# 2_classyTKL_EC_matrix.net
KiCad netlist of a schematic drawn in Altium Designer
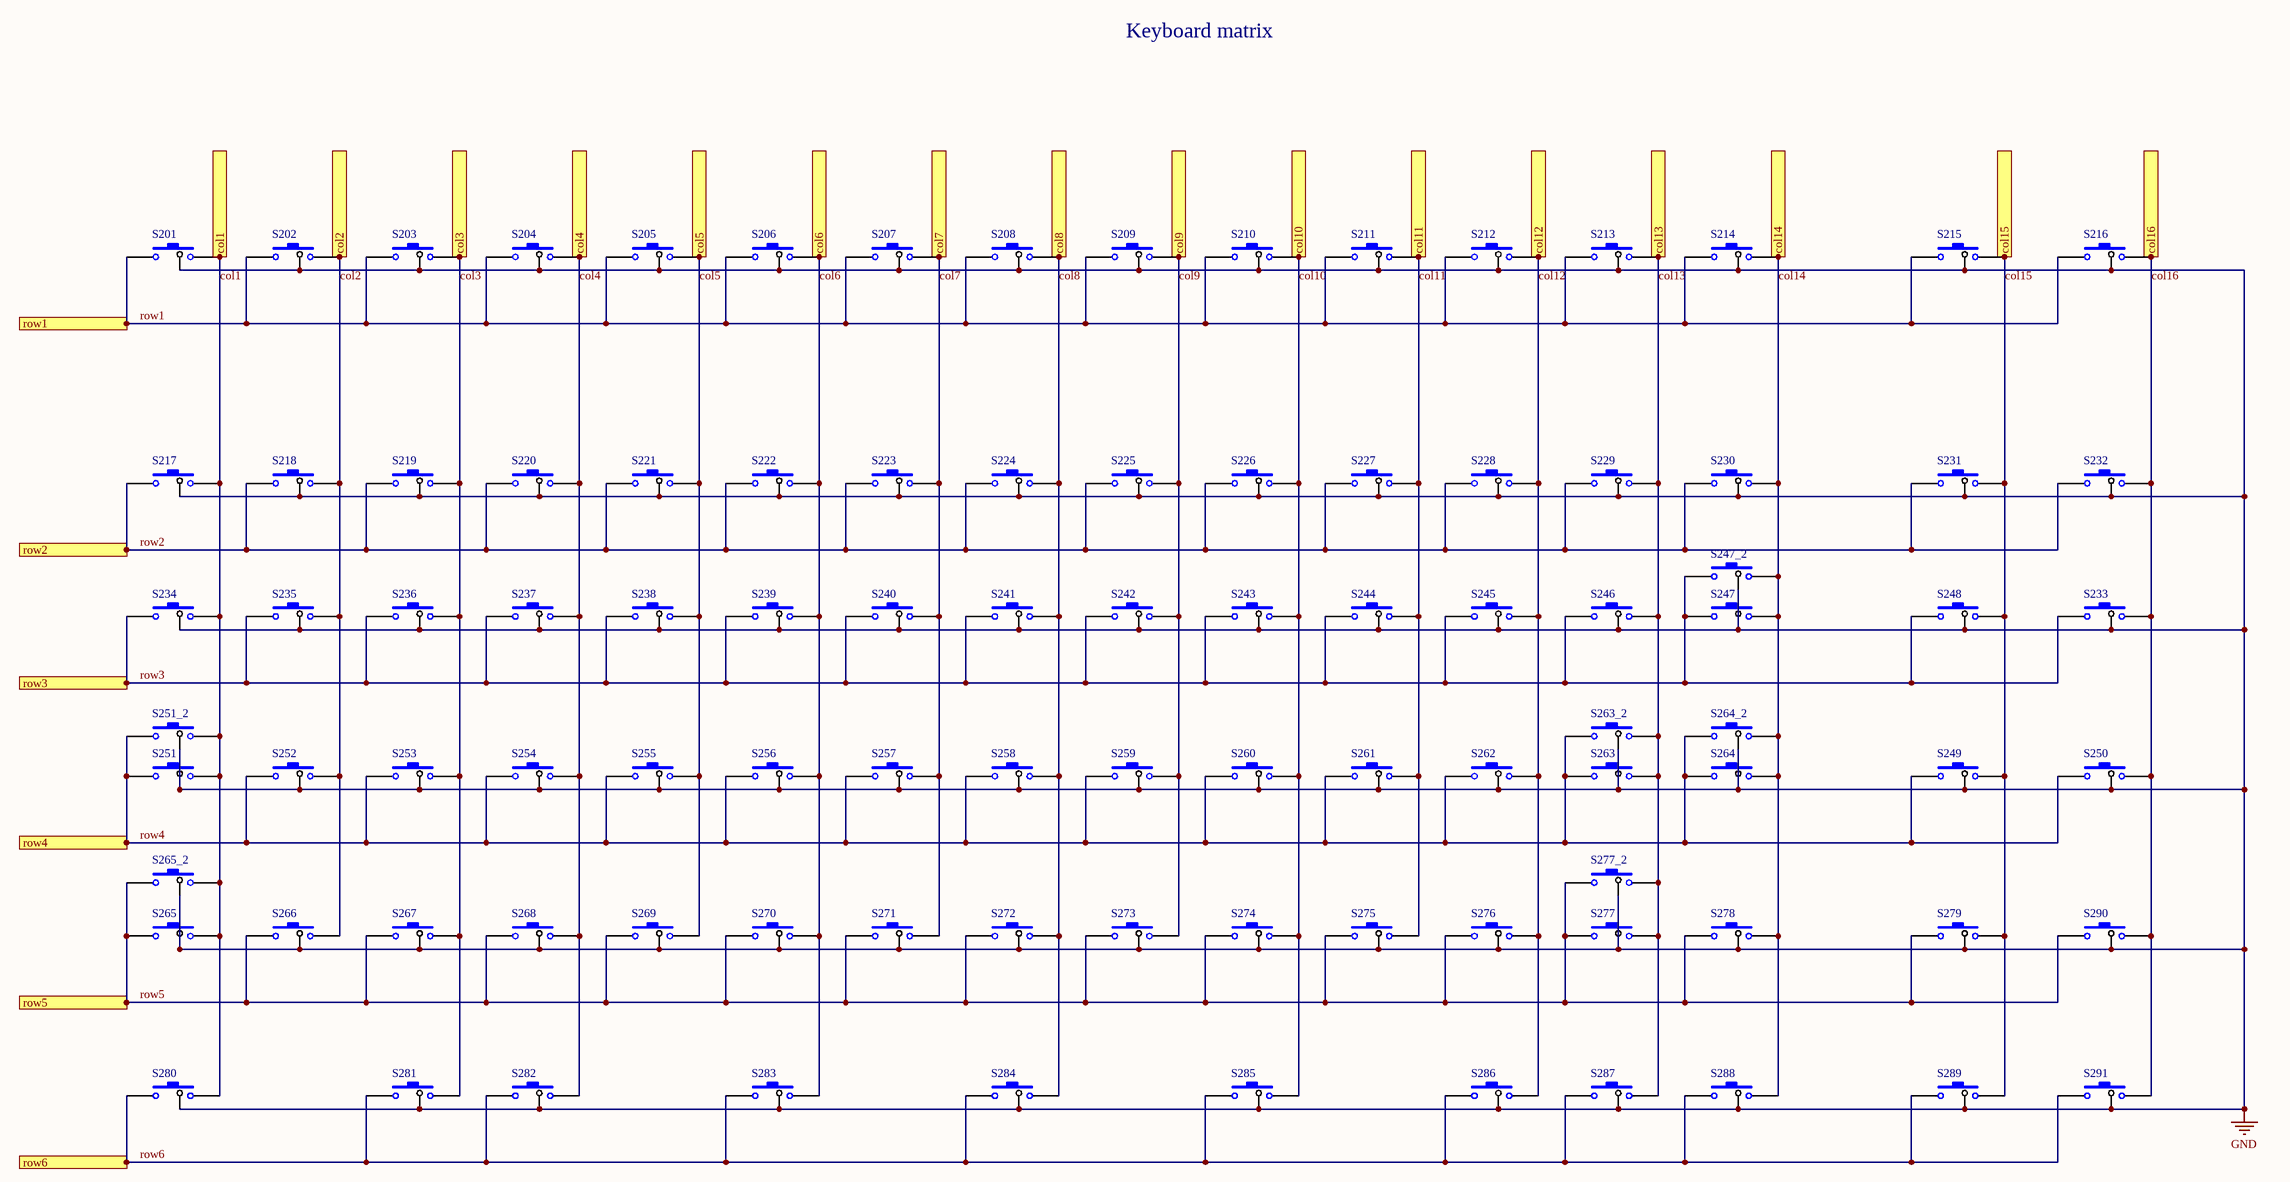
[diagram p0: 2_classyTKL_EC_matrix.SchDoc]

(export (version "E")
  (design (tool "Eeschema 10.0.6"))
  (components
    (comp (ref "S201")
      (value "SW-PB-3")
      (footprint "Topre")
      (description "Switch")
      (libsource (lib "Keebs") (part "SW-PB-3"))
    )
    (comp (ref "S202")
      (value "SW-PB-3")
      (footprint "Topre")
      (description "Switch")
      (libsource (lib "Keebs") (part "SW-PB-3"))
    )
    (comp (ref "S203")
      (value "SW-PB-3")
      (footprint "Topre")
      (description "Switch")
      (libsource (lib "Keebs") (part "SW-PB-3"))
    )
    (comp (ref "S204")
      (value "SW-PB-3")
      (footprint "Topre")
      (description "Switch")
      (libsource (lib "Keebs") (part "SW-PB-3"))
    )
    (comp (ref "S205")
      (value "SW-PB-3")
      (footprint "Topre")
      (description "Switch")
      (libsource (lib "Keebs") (part "SW-PB-3"))
    )
    (comp (ref "S206")
      (value "SW-PB-3")
      (footprint "Topre")
      (description "Switch")
      (libsource (lib "Keebs") (part "SW-PB-3"))
    )
    (comp (ref "S207")
      (value "SW-PB-3")
      (footprint "Topre")
      (description "Switch")
      (libsource (lib "Keebs") (part "SW-PB-3"))
    )
    (comp (ref "S208")
      (value "SW-PB-3")
      (footprint "Topre")
      (description "Switch")
      (libsource (lib "Keebs") (part "SW-PB-3"))
    )
    (comp (ref "S209")
      (value "SW-PB-3")
      (footprint "Topre")
      (description "Switch")
      (libsource (lib "Keebs") (part "SW-PB-3"))
    )
    (comp (ref "S210")
      (value "SW-PB-3")
      (footprint "Topre")
      (description "Switch")
      (libsource (lib "Keebs") (part "SW-PB-3"))
    )
    (comp (ref "S211")
      (value "SW-PB-3")
      (footprint "Topre")
      (description "Switch")
      (libsource (lib "Keebs") (part "SW-PB-3"))
    )
    (comp (ref "S212")
      (value "SW-PB-3")
      (footprint "Topre")
      (description "Switch")
      (libsource (lib "Keebs") (part "SW-PB-3"))
    )
    (comp (ref "S213")
      (value "SW-PB-3")
      (footprint "Topre")
      (description "Switch")
      (libsource (lib "Keebs") (part "SW-PB-3"))
    )
    (comp (ref "S214")
      (value "SW-PB-3")
      (footprint "Topre")
      (description "Switch")
      (libsource (lib "Keebs") (part "SW-PB-3"))
    )
    (comp (ref "S215")
      (value "SW-PB-3")
      (footprint "Topre")
      (description "Switch")
      (libsource (lib "Keebs") (part "SW-PB-3"))
    )
    (comp (ref "S216")
      (value "SW-PB-3")
      (footprint "Topre")
      (description "Switch")
      (libsource (lib "Keebs") (part "SW-PB-3"))
    )
    (comp (ref "S217")
      (value "SW-PB-3")
      (footprint "Topre")
      (description "Switch")
      (libsource (lib "Keebs") (part "SW-PB-3"))
    )
    (comp (ref "S218")
      (value "SW-PB-3")
      (footprint "Topre")
      (description "Switch")
      (libsource (lib "Keebs") (part "SW-PB-3"))
    )
    (comp (ref "S219")
      (value "SW-PB-3")
      (footprint "Topre")
      (description "Switch")
      (libsource (lib "Keebs") (part "SW-PB-3"))
    )
    (comp (ref "S220")
      (value "SW-PB-3")
      (footprint "Topre")
      (description "Switch")
      (libsource (lib "Keebs") (part "SW-PB-3"))
    )
    (comp (ref "S221")
      (value "SW-PB-3")
      (footprint "Topre")
      (description "Switch")
      (libsource (lib "Keebs") (part "SW-PB-3"))
    )
    (comp (ref "S222")
      (value "SW-PB-3")
      (footprint "Topre")
      (description "Switch")
      (libsource (lib "Keebs") (part "SW-PB-3"))
    )
    (comp (ref "S223")
      (value "SW-PB-3")
      (footprint "Topre")
      (description "Switch")
      (libsource (lib "Keebs") (part "SW-PB-3"))
    )
    (comp (ref "S224")
      (value "SW-PB-3")
      (footprint "Topre")
      (description "Switch")
      (libsource (lib "Keebs") (part "SW-PB-3"))
    )
    (comp (ref "S225")
      (value "SW-PB-3")
      (footprint "Topre")
      (description "Switch")
      (libsource (lib "Keebs") (part "SW-PB-3"))
    )
    (comp (ref "S226")
      (value "SW-PB-3")
      (footprint "Topre")
      (description "Switch")
      (libsource (lib "Keebs") (part "SW-PB-3"))
    )
    (comp (ref "S227")
      (value "SW-PB-3")
      (footprint "Topre")
      (description "Switch")
      (libsource (lib "Keebs") (part "SW-PB-3"))
    )
    (comp (ref "S228")
      (value "SW-PB-3")
      (footprint "Topre")
      (description "Switch")
      (libsource (lib "Keebs") (part "SW-PB-3"))
    )
    (comp (ref "S229")
      (value "SW-PB-3")
      (footprint "Topre")
      (description "Switch")
      (libsource (lib "Keebs") (part "SW-PB-3"))
    )
    (comp (ref "S230")
      (value "SW-PB-3")
      (footprint "Topre")
      (description "Switch")
      (libsource (lib "Keebs") (part "SW-PB-3"))
    )
    (comp (ref "S231")
      (value "SW-PB-3")
      (footprint "Topre")
      (description "Switch")
      (libsource (lib "Keebs") (part "SW-PB-3"))
    )
    (comp (ref "S232")
      (value "SW-PB-3")
      (footprint "Topre")
      (description "Switch")
      (libsource (lib "Keebs") (part "SW-PB-3"))
    )
    (comp (ref "S233")
      (value "SW-PB-3")
      (footprint "Topre")
      (description "Switch")
      (libsource (lib "Keebs") (part "SW-PB-3"))
    )
    (comp (ref "S234")
      (value "SW-PB-3")
      (footprint "Topre")
      (description "Switch")
      (libsource (lib "Keebs") (part "SW-PB-3"))
    )
    (comp (ref "S235")
      (value "SW-PB-3")
      (footprint "Topre")
      (description "Switch")
      (libsource (lib "Keebs") (part "SW-PB-3"))
    )
    (comp (ref "S236")
      (value "SW-PB-3")
      (footprint "Topre")
      (description "Switch")
      (libsource (lib "Keebs") (part "SW-PB-3"))
    )
    (comp (ref "S237")
      (value "SW-PB-3")
      (footprint "Topre")
      (description "Switch")
      (libsource (lib "Keebs") (part "SW-PB-3"))
    )
    (comp (ref "S238")
      (value "SW-PB-3")
      (footprint "Topre")
      (description "Switch")
      (libsource (lib "Keebs") (part "SW-PB-3"))
    )
    (comp (ref "S239")
      (value "SW-PB-3")
      (footprint "Topre")
      (description "Switch")
      (libsource (lib "Keebs") (part "SW-PB-3"))
    )
    (comp (ref "S240")
      (value "SW-PB-3")
      (footprint "Topre")
      (description "Switch")
      (libsource (lib "Keebs") (part "SW-PB-3"))
    )
    (comp (ref "S241")
      (value "SW-PB-3")
      (footprint "Topre")
      (description "Switch")
      (libsource (lib "Keebs") (part "SW-PB-3"))
    )
    (comp (ref "S242")
      (value "SW-PB-3")
      (footprint "Topre")
      (description "Switch")
      (libsource (lib "Keebs") (part "SW-PB-3"))
    )
    (comp (ref "S243")
      (value "SW-PB-3")
      (footprint "Topre")
      (description "Switch")
      (libsource (lib "Keebs") (part "SW-PB-3"))
    )
    (comp (ref "S244")
      (value "SW-PB-3")
      (footprint "Topre")
      (description "Switch")
      (libsource (lib "Keebs") (part "SW-PB-3"))
    )
    (comp (ref "S245")
      (value "SW-PB-3")
      (footprint "Topre")
      (description "Switch")
      (libsource (lib "Keebs") (part "SW-PB-3"))
    )
    (comp (ref "S246")
      (value "SW-PB-3")
      (footprint "Topre")
      (description "Switch")
      (libsource (lib "Keebs") (part "SW-PB-3"))
    )
    (comp (ref "S247")
      (value "SW-PB-3")
      (footprint "Topre")
      (description "Switch")
      (libsource (lib "Keebs") (part "SW-PB-3"))
    )
    (comp (ref "S247_2")
      (value "SW-PB-3")
      (footprint "Topre")
      (description "Switch")
      (libsource (lib "Keebs") (part "SW-PB-3"))
    )
    (comp (ref "S248")
      (value "SW-PB-3")
      (footprint "Topre")
      (description "Switch")
      (libsource (lib "Keebs") (part "SW-PB-3"))
    )
    (comp (ref "S249")
      (value "SW-PB-3")
      (footprint "Topre")
      (description "Switch")
      (libsource (lib "Keebs") (part "SW-PB-3"))
    )
    (comp (ref "S250")
      (value "SW-PB-3")
      (footprint "Topre")
      (description "Switch")
      (libsource (lib "Keebs") (part "SW-PB-3"))
    )
    (comp (ref "S251")
      (value "SW-PB-3")
      (footprint "Topre")
      (description "Switch")
      (libsource (lib "Keebs") (part "SW-PB-3"))
    )
    (comp (ref "S251_2")
      (value "SW-PB-3")
      (footprint "Topre")
      (description "Switch")
      (libsource (lib "Keebs") (part "SW-PB-3"))
    )
    (comp (ref "S252")
      (value "SW-PB-3")
      (footprint "Topre")
      (description "Switch")
      (libsource (lib "Keebs") (part "SW-PB-3"))
    )
    (comp (ref "S253")
      (value "SW-PB-3")
      (footprint "Topre")
      (description "Switch")
      (libsource (lib "Keebs") (part "SW-PB-3"))
    )
    (comp (ref "S254")
      (value "SW-PB-3")
      (footprint "Topre")
      (description "Switch")
      (libsource (lib "Keebs") (part "SW-PB-3"))
    )
    (comp (ref "S255")
      (value "SW-PB-3")
      (footprint "Topre")
      (description "Switch")
      (libsource (lib "Keebs") (part "SW-PB-3"))
    )
    (comp (ref "S256")
      (value "SW-PB-3")
      (footprint "Topre")
      (description "Switch")
      (libsource (lib "Keebs") (part "SW-PB-3"))
    )
    (comp (ref "S257")
      (value "SW-PB-3")
      (footprint "Topre")
      (description "Switch")
      (libsource (lib "Keebs") (part "SW-PB-3"))
    )
    (comp (ref "S258")
      (value "SW-PB-3")
      (footprint "Topre")
      (description "Switch")
      (libsource (lib "Keebs") (part "SW-PB-3"))
    )
    (comp (ref "S259")
      (value "SW-PB-3")
      (footprint "Topre")
      (description "Switch")
      (libsource (lib "Keebs") (part "SW-PB-3"))
    )
    (comp (ref "S260")
      (value "SW-PB-3")
      (footprint "Topre")
      (description "Switch")
      (libsource (lib "Keebs") (part "SW-PB-3"))
    )
    (comp (ref "S261")
      (value "SW-PB-3")
      (footprint "Topre")
      (description "Switch")
      (libsource (lib "Keebs") (part "SW-PB-3"))
    )
    (comp (ref "S262")
      (value "SW-PB-3")
      (footprint "Topre")
      (description "Switch")
      (libsource (lib "Keebs") (part "SW-PB-3"))
    )
    (comp (ref "S263")
      (value "SW-PB-3")
      (footprint "Topre")
      (description "Switch")
      (libsource (lib "Keebs") (part "SW-PB-3"))
    )
    (comp (ref "S263_2")
      (value "SW-PB-3")
      (footprint "Topre")
      (description "Switch")
      (libsource (lib "Keebs") (part "SW-PB-3"))
    )
    (comp (ref "S264")
      (value "SW-PB-3")
      (footprint "Topre")
      (description "Switch")
      (libsource (lib "Keebs") (part "SW-PB-3"))
    )
    (comp (ref "S264_2")
      (value "SW-PB-3")
      (footprint "Topre")
      (description "Switch")
      (libsource (lib "Keebs") (part "SW-PB-3"))
    )
    (comp (ref "S265")
      (value "SW-PB-3")
      (footprint "Topre")
      (description "Switch")
      (libsource (lib "Keebs") (part "SW-PB-3"))
    )
    (comp (ref "S265_2")
      (value "SW-PB-3")
      (footprint "Topre")
      (description "Switch")
      (libsource (lib "Keebs") (part "SW-PB-3"))
    )
    (comp (ref "S266")
      (value "SW-PB-3")
      (footprint "Topre")
      (description "Switch")
      (libsource (lib "Keebs") (part "SW-PB-3"))
    )
    (comp (ref "S267")
      (value "SW-PB-3")
      (footprint "Topre")
      (description "Switch")
      (libsource (lib "Keebs") (part "SW-PB-3"))
    )
    (comp (ref "S268")
      (value "SW-PB-3")
      (footprint "Topre")
      (description "Switch")
      (libsource (lib "Keebs") (part "SW-PB-3"))
    )
    (comp (ref "S269")
      (value "SW-PB-3")
      (footprint "Topre")
      (description "Switch")
      (libsource (lib "Keebs") (part "SW-PB-3"))
    )
    (comp (ref "S270")
      (value "SW-PB-3")
      (footprint "Topre")
      (description "Switch")
      (libsource (lib "Keebs") (part "SW-PB-3"))
    )
    (comp (ref "S271")
      (value "SW-PB-3")
      (footprint "Topre")
      (description "Switch")
      (libsource (lib "Keebs") (part "SW-PB-3"))
    )
    (comp (ref "S272")
      (value "SW-PB-3")
      (footprint "Topre")
      (description "Switch")
      (libsource (lib "Keebs") (part "SW-PB-3"))
    )
    (comp (ref "S273")
      (value "SW-PB-3")
      (footprint "Topre")
      (description "Switch")
      (libsource (lib "Keebs") (part "SW-PB-3"))
    )
    (comp (ref "S274")
      (value "SW-PB-3")
      (footprint "Topre")
      (description "Switch")
      (libsource (lib "Keebs") (part "SW-PB-3"))
    )
    (comp (ref "S275")
      (value "SW-PB-3")
      (footprint "Topre")
      (description "Switch")
      (libsource (lib "Keebs") (part "SW-PB-3"))
    )
    (comp (ref "S276")
      (value "SW-PB-3")
      (footprint "Topre")
      (description "Switch")
      (libsource (lib "Keebs") (part "SW-PB-3"))
    )
    (comp (ref "S277")
      (value "SW-PB-3")
      (footprint "Topre")
      (description "Switch")
      (libsource (lib "Keebs") (part "SW-PB-3"))
    )
    (comp (ref "S277_2")
      (value "SW-PB-3")
      (footprint "Topre")
      (description "Switch")
      (libsource (lib "Keebs") (part "SW-PB-3"))
    )
    (comp (ref "S278")
      (value "SW-PB-3")
      (footprint "Topre")
      (description "Switch")
      (libsource (lib "Keebs") (part "SW-PB-3"))
    )
    (comp (ref "S279")
      (value "SW-PB-3")
      (footprint "Topre")
      (description "Switch")
      (libsource (lib "Keebs") (part "SW-PB-3"))
    )
    (comp (ref "S280")
      (value "SW-PB-3")
      (footprint "Topre")
      (description "Switch")
      (libsource (lib "Keebs") (part "SW-PB-3"))
    )
    (comp (ref "S281")
      (value "SW-PB-3")
      (footprint "Topre")
      (description "Switch")
      (libsource (lib "Keebs") (part "SW-PB-3"))
    )
    (comp (ref "S282")
      (value "SW-PB-3")
      (footprint "Topre")
      (description "Switch")
      (libsource (lib "Keebs") (part "SW-PB-3"))
    )
    (comp (ref "S283")
      (value "SW-PB-3")
      (footprint "Topre")
      (description "Switch")
      (libsource (lib "Keebs") (part "SW-PB-3"))
    )
    (comp (ref "S284")
      (value "SW-PB-3")
      (footprint "Topre")
      (description "Switch")
      (libsource (lib "Keebs") (part "SW-PB-3"))
    )
    (comp (ref "S285")
      (value "SW-PB-3")
      (footprint "Topre")
      (description "Switch")
      (libsource (lib "Keebs") (part "SW-PB-3"))
    )
    (comp (ref "S286")
      (value "SW-PB-3")
      (footprint "Topre")
      (description "Switch")
      (libsource (lib "Keebs") (part "SW-PB-3"))
    )
    (comp (ref "S287")
      (value "SW-PB-3")
      (footprint "Topre")
      (description "Switch")
      (libsource (lib "Keebs") (part "SW-PB-3"))
    )
    (comp (ref "S288")
      (value "SW-PB-3")
      (footprint "Topre")
      (description "Switch")
      (libsource (lib "Keebs") (part "SW-PB-3"))
    )
    (comp (ref "S289")
      (value "SW-PB-3")
      (footprint "Topre")
      (description "Switch")
      (libsource (lib "Keebs") (part "SW-PB-3"))
    )
    (comp (ref "S290")
      (value "SW-PB-3")
      (footprint "Topre")
      (description "Switch")
      (libsource (lib "Keebs") (part "SW-PB-3"))
    )
    (comp (ref "S291")
      (value "SW-PB-3")
      (footprint "Topre")
      (description "Switch")
      (libsource (lib "Keebs") (part "SW-PB-3"))
    )
  )
  (nets
    (net (code "1") (name "/col1") (class "Default")
      (node (ref "S201") (pin "2") (pinfunction "2_2") (pintype "passive"))
      (node (ref "S217") (pin "2") (pinfunction "2_2") (pintype "passive"))
      (node (ref "S234") (pin "2") (pinfunction "2_2") (pintype "passive"))
      (node (ref "S251") (pin "2") (pinfunction "2_2") (pintype "passive"))
      (node (ref "S251_2") (pin "2") (pinfunction "2_2") (pintype "passive"))
      (node (ref "S265") (pin "2") (pinfunction "2_2") (pintype "passive"))
      (node (ref "S265_2") (pin "2") (pinfunction "2_2") (pintype "passive"))
      (node (ref "S280") (pin "2") (pinfunction "2_2") (pintype "passive"))
    )
    (net (code "2") (name "/col2") (class "Default")
      (node (ref "S202") (pin "2") (pinfunction "2_2") (pintype "passive"))
      (node (ref "S218") (pin "2") (pinfunction "2_2") (pintype "passive"))
      (node (ref "S235") (pin "2") (pinfunction "2_2") (pintype "passive"))
      (node (ref "S252") (pin "2") (pinfunction "2_2") (pintype "passive"))
      (node (ref "S266") (pin "2") (pinfunction "2_2") (pintype "passive"))
    )
    (net (code "3") (name "/col3") (class "Default")
      (node (ref "S203") (pin "2") (pinfunction "2_2") (pintype "passive"))
      (node (ref "S219") (pin "2") (pinfunction "2_2") (pintype "passive"))
      (node (ref "S236") (pin "2") (pinfunction "2_2") (pintype "passive"))
      (node (ref "S253") (pin "2") (pinfunction "2_2") (pintype "passive"))
      (node (ref "S267") (pin "2") (pinfunction "2_2") (pintype "passive"))
      (node (ref "S281") (pin "2") (pinfunction "2_2") (pintype "passive"))
    )
    (net (code "4") (name "/col4") (class "Default")
      (node (ref "S204") (pin "2") (pinfunction "2_2") (pintype "passive"))
      (node (ref "S220") (pin "2") (pinfunction "2_2") (pintype "passive"))
      (node (ref "S237") (pin "2") (pinfunction "2_2") (pintype "passive"))
      (node (ref "S254") (pin "2") (pinfunction "2_2") (pintype "passive"))
      (node (ref "S268") (pin "2") (pinfunction "2_2") (pintype "passive"))
      (node (ref "S282") (pin "2") (pinfunction "2_2") (pintype "passive"))
    )
    (net (code "5") (name "/col5") (class "Default")
      (node (ref "S205") (pin "2") (pinfunction "2_2") (pintype "passive"))
      (node (ref "S221") (pin "2") (pinfunction "2_2") (pintype "passive"))
      (node (ref "S238") (pin "2") (pinfunction "2_2") (pintype "passive"))
      (node (ref "S255") (pin "2") (pinfunction "2_2") (pintype "passive"))
      (node (ref "S269") (pin "2") (pinfunction "2_2") (pintype "passive"))
    )
    (net (code "6") (name "/col6") (class "Default")
      (node (ref "S206") (pin "2") (pinfunction "2_2") (pintype "passive"))
      (node (ref "S222") (pin "2") (pinfunction "2_2") (pintype "passive"))
      (node (ref "S239") (pin "2") (pinfunction "2_2") (pintype "passive"))
      (node (ref "S256") (pin "2") (pinfunction "2_2") (pintype "passive"))
      (node (ref "S270") (pin "2") (pinfunction "2_2") (pintype "passive"))
      (node (ref "S283") (pin "2") (pinfunction "2_2") (pintype "passive"))
    )
    (net (code "7") (name "/col7") (class "Default")
      (node (ref "S207") (pin "2") (pinfunction "2_2") (pintype "passive"))
      (node (ref "S223") (pin "2") (pinfunction "2_2") (pintype "passive"))
      (node (ref "S240") (pin "2") (pinfunction "2_2") (pintype "passive"))
      (node (ref "S257") (pin "2") (pinfunction "2_2") (pintype "passive"))
      (node (ref "S271") (pin "2") (pinfunction "2_2") (pintype "passive"))
    )
    (net (code "8") (name "/col8") (class "Default")
      (node (ref "S208") (pin "2") (pinfunction "2_2") (pintype "passive"))
      (node (ref "S224") (pin "2") (pinfunction "2_2") (pintype "passive"))
      (node (ref "S241") (pin "2") (pinfunction "2_2") (pintype "passive"))
      (node (ref "S258") (pin "2") (pinfunction "2_2") (pintype "passive"))
      (node (ref "S272") (pin "2") (pinfunction "2_2") (pintype "passive"))
      (node (ref "S284") (pin "2") (pinfunction "2_2") (pintype "passive"))
    )
    (net (code "9") (name "/col9") (class "Default")
      (node (ref "S209") (pin "2") (pinfunction "2_2") (pintype "passive"))
      (node (ref "S225") (pin "2") (pinfunction "2_2") (pintype "passive"))
      (node (ref "S242") (pin "2") (pinfunction "2_2") (pintype "passive"))
      (node (ref "S259") (pin "2") (pinfunction "2_2") (pintype "passive"))
      (node (ref "S273") (pin "2") (pinfunction "2_2") (pintype "passive"))
    )
    (net (code "10") (name "/col10") (class "Default")
      (node (ref "S210") (pin "2") (pinfunction "2_2") (pintype "passive"))
      (node (ref "S226") (pin "2") (pinfunction "2_2") (pintype "passive"))
      (node (ref "S243") (pin "2") (pinfunction "2_2") (pintype "passive"))
      (node (ref "S260") (pin "2") (pinfunction "2_2") (pintype "passive"))
      (node (ref "S274") (pin "2") (pinfunction "2_2") (pintype "passive"))
      (node (ref "S285") (pin "2") (pinfunction "2_2") (pintype "passive"))
    )
    (net (code "11") (name "/col11") (class "Default")
      (node (ref "S211") (pin "2") (pinfunction "2_2") (pintype "passive"))
      (node (ref "S227") (pin "2") (pinfunction "2_2") (pintype "passive"))
      (node (ref "S244") (pin "2") (pinfunction "2_2") (pintype "passive"))
      (node (ref "S261") (pin "2") (pinfunction "2_2") (pintype "passive"))
      (node (ref "S275") (pin "2") (pinfunction "2_2") (pintype "passive"))
    )
    (net (code "12") (name "/col12") (class "Default")
      (node (ref "S212") (pin "2") (pinfunction "2_2") (pintype "passive"))
      (node (ref "S228") (pin "2") (pinfunction "2_2") (pintype "passive"))
      (node (ref "S245") (pin "2") (pinfunction "2_2") (pintype "passive"))
      (node (ref "S262") (pin "2") (pinfunction "2_2") (pintype "passive"))
      (node (ref "S276") (pin "2") (pinfunction "2_2") (pintype "passive"))
      (node (ref "S286") (pin "2") (pinfunction "2_2") (pintype "passive"))
    )
    (net (code "13") (name "/col13") (class "Default")
      (node (ref "S213") (pin "2") (pinfunction "2_2") (pintype "passive"))
      (node (ref "S229") (pin "2") (pinfunction "2_2") (pintype "passive"))
      (node (ref "S246") (pin "2") (pinfunction "2_2") (pintype "passive"))
      (node (ref "S263") (pin "2") (pinfunction "2_2") (pintype "passive"))
      (node (ref "S263_2") (pin "2") (pinfunction "2_2") (pintype "passive"))
      (node (ref "S277") (pin "2") (pinfunction "2_2") (pintype "passive"))
      (node (ref "S277_2") (pin "2") (pinfunction "2_2") (pintype "passive"))
      (node (ref "S287") (pin "2") (pinfunction "2_2") (pintype "passive"))
    )
    (net (code "14") (name "/col14") (class "Default")
      (node (ref "S214") (pin "2") (pinfunction "2_2") (pintype "passive"))
      (node (ref "S230") (pin "2") (pinfunction "2_2") (pintype "passive"))
      (node (ref "S247") (pin "2") (pinfunction "2_2") (pintype "passive"))
      (node (ref "S247_2") (pin "2") (pinfunction "2_2") (pintype "passive"))
      (node (ref "S264") (pin "2") (pinfunction "2_2") (pintype "passive"))
      (node (ref "S264_2") (pin "2") (pinfunction "2_2") (pintype "passive"))
      (node (ref "S278") (pin "2") (pinfunction "2_2") (pintype "passive"))
      (node (ref "S288") (pin "2") (pinfunction "2_2") (pintype "passive"))
    )
    (net (code "15") (name "/col15") (class "Default")
      (node (ref "S215") (pin "2") (pinfunction "2_2") (pintype "passive"))
      (node (ref "S231") (pin "2") (pinfunction "2_2") (pintype "passive"))
      (node (ref "S248") (pin "2") (pinfunction "2_2") (pintype "passive"))
      (node (ref "S249") (pin "2") (pinfunction "2_2") (pintype "passive"))
      (node (ref "S279") (pin "2") (pinfunction "2_2") (pintype "passive"))
      (node (ref "S289") (pin "2") (pinfunction "2_2") (pintype "passive"))
    )
    (net (code "16") (name "/col16") (class "Default")
      (node (ref "S216") (pin "2") (pinfunction "2_2") (pintype "passive"))
      (node (ref "S232") (pin "2") (pinfunction "2_2") (pintype "passive"))
      (node (ref "S233") (pin "2") (pinfunction "2_2") (pintype "passive"))
      (node (ref "S250") (pin "2") (pinfunction "2_2") (pintype "passive"))
      (node (ref "S290") (pin "2") (pinfunction "2_2") (pintype "passive"))
      (node (ref "S291") (pin "2") (pinfunction "2_2") (pintype "passive"))
    )
    (net (code "17") (name "/row1") (class "Default")
      (node (ref "S201") (pin "1") (pinfunction "1_1") (pintype "passive"))
      (node (ref "S202") (pin "1") (pinfunction "1_1") (pintype "passive"))
      (node (ref "S203") (pin "1") (pinfunction "1_1") (pintype "passive"))
      (node (ref "S204") (pin "1") (pinfunction "1_1") (pintype "passive"))
      (node (ref "S205") (pin "1") (pinfunction "1_1") (pintype "passive"))
      (node (ref "S206") (pin "1") (pinfunction "1_1") (pintype "passive"))
      (node (ref "S207") (pin "1") (pinfunction "1_1") (pintype "passive"))
      (node (ref "S208") (pin "1") (pinfunction "1_1") (pintype "passive"))
      (node (ref "S209") (pin "1") (pinfunction "1_1") (pintype "passive"))
      (node (ref "S210") (pin "1") (pinfunction "1_1") (pintype "passive"))
      (node (ref "S211") (pin "1") (pinfunction "1_1") (pintype "passive"))
      (node (ref "S212") (pin "1") (pinfunction "1_1") (pintype "passive"))
      (node (ref "S213") (pin "1") (pinfunction "1_1") (pintype "passive"))
      (node (ref "S214") (pin "1") (pinfunction "1_1") (pintype "passive"))
      (node (ref "S215") (pin "1") (pinfunction "1_1") (pintype "passive"))
      (node (ref "S216") (pin "1") (pinfunction "1_1") (pintype "passive"))
    )
    (net (code "18") (name "/row2") (class "Default")
      (node (ref "S217") (pin "1") (pinfunction "1_1") (pintype "passive"))
      (node (ref "S218") (pin "1") (pinfunction "1_1") (pintype "passive"))
      (node (ref "S219") (pin "1") (pinfunction "1_1") (pintype "passive"))
      (node (ref "S220") (pin "1") (pinfunction "1_1") (pintype "passive"))
      (node (ref "S221") (pin "1") (pinfunction "1_1") (pintype "passive"))
      (node (ref "S222") (pin "1") (pinfunction "1_1") (pintype "passive"))
      (node (ref "S223") (pin "1") (pinfunction "1_1") (pintype "passive"))
      (node (ref "S224") (pin "1") (pinfunction "1_1") (pintype "passive"))
      (node (ref "S225") (pin "1") (pinfunction "1_1") (pintype "passive"))
      (node (ref "S226") (pin "1") (pinfunction "1_1") (pintype "passive"))
      (node (ref "S227") (pin "1") (pinfunction "1_1") (pintype "passive"))
      (node (ref "S228") (pin "1") (pinfunction "1_1") (pintype "passive"))
      (node (ref "S229") (pin "1") (pinfunction "1_1") (pintype "passive"))
      (node (ref "S230") (pin "1") (pinfunction "1_1") (pintype "passive"))
      (node (ref "S231") (pin "1") (pinfunction "1_1") (pintype "passive"))
      (node (ref "S232") (pin "1") (pinfunction "1_1") (pintype "passive"))
    )
    (net (code "19") (name "/row3") (class "Default")
      (node (ref "S233") (pin "1") (pinfunction "1_1") (pintype "passive"))
      (node (ref "S234") (pin "1") (pinfunction "1_1") (pintype "passive"))
      (node (ref "S235") (pin "1") (pinfunction "1_1") (pintype "passive"))
      (node (ref "S236") (pin "1") (pinfunction "1_1") (pintype "passive"))
      (node (ref "S237") (pin "1") (pinfunction "1_1") (pintype "passive"))
      (node (ref "S238") (pin "1") (pinfunction "1_1") (pintype "passive"))
      (node (ref "S239") (pin "1") (pinfunction "1_1") (pintype "passive"))
      (node (ref "S240") (pin "1") (pinfunction "1_1") (pintype "passive"))
      (node (ref "S241") (pin "1") (pinfunction "1_1") (pintype "passive"))
      (node (ref "S242") (pin "1") (pinfunction "1_1") (pintype "passive"))
      (node (ref "S243") (pin "1") (pinfunction "1_1") (pintype "passive"))
      (node (ref "S244") (pin "1") (pinfunction "1_1") (pintype "passive"))
      (node (ref "S245") (pin "1") (pinfunction "1_1") (pintype "passive"))
      (node (ref "S246") (pin "1") (pinfunction "1_1") (pintype "passive"))
      (node (ref "S247") (pin "1") (pinfunction "1_1") (pintype "passive"))
      (node (ref "S247_2") (pin "1") (pinfunction "1_1") (pintype "passive"))
      (node (ref "S248") (pin "1") (pinfunction "1_1") (pintype "passive"))
    )
    (net (code "20") (name "/row4") (class "Default")
      (node (ref "S249") (pin "1") (pinfunction "1_1") (pintype "passive"))
      (node (ref "S250") (pin "1") (pinfunction "1_1") (pintype "passive"))
      (node (ref "S251") (pin "1") (pinfunction "1_1") (pintype "passive"))
      (node (ref "S251_2") (pin "1") (pinfunction "1_1") (pintype "passive"))
      (node (ref "S252") (pin "1") (pinfunction "1_1") (pintype "passive"))
      (node (ref "S253") (pin "1") (pinfunction "1_1") (pintype "passive"))
      (node (ref "S254") (pin "1") (pinfunction "1_1") (pintype "passive"))
      (node (ref "S255") (pin "1") (pinfunction "1_1") (pintype "passive"))
      (node (ref "S256") (pin "1") (pinfunction "1_1") (pintype "passive"))
      (node (ref "S257") (pin "1") (pinfunction "1_1") (pintype "passive"))
      (node (ref "S258") (pin "1") (pinfunction "1_1") (pintype "passive"))
      (node (ref "S259") (pin "1") (pinfunction "1_1") (pintype "passive"))
      (node (ref "S260") (pin "1") (pinfunction "1_1") (pintype "passive"))
      (node (ref "S261") (pin "1") (pinfunction "1_1") (pintype "passive"))
      (node (ref "S262") (pin "1") (pinfunction "1_1") (pintype "passive"))
      (node (ref "S263") (pin "1") (pinfunction "1_1") (pintype "passive"))
      (node (ref "S263_2") (pin "1") (pinfunction "1_1") (pintype "passive"))
      (node (ref "S264") (pin "1") (pinfunction "1_1") (pintype "passive"))
      (node (ref "S264_2") (pin "1") (pinfunction "1_1") (pintype "passive"))
    )
    (net (code "21") (name "/row5") (class "Default")
      (node (ref "S265") (pin "1") (pinfunction "1_1") (pintype "passive"))
      (node (ref "S265_2") (pin "1") (pinfunction "1_1") (pintype "passive"))
      (node (ref "S266") (pin "1") (pinfunction "1_1") (pintype "passive"))
      (node (ref "S267") (pin "1") (pinfunction "1_1") (pintype "passive"))
      (node (ref "S268") (pin "1") (pinfunction "1_1") (pintype "passive"))
      (node (ref "S269") (pin "1") (pinfunction "1_1") (pintype "passive"))
      (node (ref "S270") (pin "1") (pinfunction "1_1") (pintype "passive"))
      (node (ref "S271") (pin "1") (pinfunction "1_1") (pintype "passive"))
      (node (ref "S272") (pin "1") (pinfunction "1_1") (pintype "passive"))
      (node (ref "S273") (pin "1") (pinfunction "1_1") (pintype "passive"))
      (node (ref "S274") (pin "1") (pinfunction "1_1") (pintype "passive"))
      (node (ref "S275") (pin "1") (pinfunction "1_1") (pintype "passive"))
      (node (ref "S276") (pin "1") (pinfunction "1_1") (pintype "passive"))
      (node (ref "S277") (pin "1") (pinfunction "1_1") (pintype "passive"))
      (node (ref "S277_2") (pin "1") (pinfunction "1_1") (pintype "passive"))
      (node (ref "S278") (pin "1") (pinfunction "1_1") (pintype "passive"))
      (node (ref "S279") (pin "1") (pinfunction "1_1") (pintype "passive"))
      (node (ref "S290") (pin "1") (pinfunction "1_1") (pintype "passive"))
    )
    (net (code "22") (name "/row6") (class "Default")
      (node (ref "S280") (pin "1") (pinfunction "1_1") (pintype "passive"))
      (node (ref "S281") (pin "1") (pinfunction "1_1") (pintype "passive"))
      (node (ref "S282") (pin "1") (pinfunction "1_1") (pintype "passive"))
      (node (ref "S283") (pin "1") (pinfunction "1_1") (pintype "passive"))
      (node (ref "S284") (pin "1") (pinfunction "1_1") (pintype "passive"))
      (node (ref "S285") (pin "1") (pinfunction "1_1") (pintype "passive"))
      (node (ref "S286") (pin "1") (pinfunction "1_1") (pintype "passive"))
      (node (ref "S287") (pin "1") (pinfunction "1_1") (pintype "passive"))
      (node (ref "S288") (pin "1") (pinfunction "1_1") (pintype "passive"))
      (node (ref "S289") (pin "1") (pinfunction "1_1") (pintype "passive"))
      (node (ref "S291") (pin "1") (pinfunction "1_1") (pintype "passive"))
    )
    (net (code "23") (name "GND") (class "Default")
      (node (ref "S201") (pin "3") (pinfunction "3_3") (pintype "passive"))
      (node (ref "S202") (pin "3") (pinfunction "3_3") (pintype "passive"))
      (node (ref "S203") (pin "3") (pinfunction "3_3") (pintype "passive"))
      (node (ref "S204") (pin "3") (pinfunction "3_3") (pintype "passive"))
      (node (ref "S205") (pin "3") (pinfunction "3_3") (pintype "passive"))
      (node (ref "S206") (pin "3") (pinfunction "3_3") (pintype "passive"))
      (node (ref "S207") (pin "3") (pinfunction "3_3") (pintype "passive"))
      (node (ref "S208") (pin "3") (pinfunction "3_3") (pintype "passive"))
      (node (ref "S209") (pin "3") (pinfunction "3_3") (pintype "passive"))
      (node (ref "S210") (pin "3") (pinfunction "3_3") (pintype "passive"))
      (node (ref "S211") (pin "3") (pinfunction "3_3") (pintype "passive"))
      (node (ref "S212") (pin "3") (pinfunction "3_3") (pintype "passive"))
      (node (ref "S213") (pin "3") (pinfunction "3_3") (pintype "passive"))
      (node (ref "S214") (pin "3") (pinfunction "3_3") (pintype "passive"))
      (node (ref "S215") (pin "3") (pinfunction "3_3") (pintype "passive"))
      (node (ref "S216") (pin "3") (pinfunction "3_3") (pintype "passive"))
      (node (ref "S217") (pin "3") (pinfunction "3_3") (pintype "passive"))
      (node (ref "S218") (pin "3") (pinfunction "3_3") (pintype "passive"))
      (node (ref "S219") (pin "3") (pinfunction "3_3") (pintype "passive"))
      (node (ref "S220") (pin "3") (pinfunction "3_3") (pintype "passive"))
      (node (ref "S221") (pin "3") (pinfunction "3_3") (pintype "passive"))
      (node (ref "S222") (pin "3") (pinfunction "3_3") (pintype "passive"))
      (node (ref "S223") (pin "3") (pinfunction "3_3") (pintype "passive"))
      (node (ref "S224") (pin "3") (pinfunction "3_3") (pintype "passive"))
      (node (ref "S225") (pin "3") (pinfunction "3_3") (pintype "passive"))
      (node (ref "S226") (pin "3") (pinfunction "3_3") (pintype "passive"))
      (node (ref "S227") (pin "3") (pinfunction "3_3") (pintype "passive"))
      (node (ref "S228") (pin "3") (pinfunction "3_3") (pintype "passive"))
      (node (ref "S229") (pin "3") (pinfunction "3_3") (pintype "passive"))
      (node (ref "S230") (pin "3") (pinfunction "3_3") (pintype "passive"))
      (node (ref "S231") (pin "3") (pinfunction "3_3") (pintype "passive"))
      (node (ref "S232") (pin "3") (pinfunction "3_3") (pintype "passive"))
      (node (ref "S233") (pin "3") (pinfunction "3_3") (pintype "passive"))
      (node (ref "S234") (pin "3") (pinfunction "3_3") (pintype "passive"))
      (node (ref "S235") (pin "3") (pinfunction "3_3") (pintype "passive"))
      (node (ref "S236") (pin "3") (pinfunction "3_3") (pintype "passive"))
      (node (ref "S237") (pin "3") (pinfunction "3_3") (pintype "passive"))
      (node (ref "S238") (pin "3") (pinfunction "3_3") (pintype "passive"))
      (node (ref "S239") (pin "3") (pinfunction "3_3") (pintype "passive"))
      (node (ref "S240") (pin "3") (pinfunction "3_3") (pintype "passive"))
      (node (ref "S241") (pin "3") (pinfunction "3_3") (pintype "passive"))
      (node (ref "S242") (pin "3") (pinfunction "3_3") (pintype "passive"))
      (node (ref "S243") (pin "3") (pinfunction "3_3") (pintype "passive"))
      (node (ref "S244") (pin "3") (pinfunction "3_3") (pintype "passive"))
      (node (ref "S245") (pin "3") (pinfunction "3_3") (pintype "passive"))
      (node (ref "S246") (pin "3") (pinfunction "3_3") (pintype "passive"))
      (node (ref "S247") (pin "3") (pinfunction "3_3") (pintype "passive"))
      (node (ref "S247_2") (pin "3") (pinfunction "3_3") (pintype "passive"))
      (node (ref "S248") (pin "3") (pinfunction "3_3") (pintype "passive"))
      (node (ref "S249") (pin "3") (pinfunction "3_3") (pintype "passive"))
      (node (ref "S250") (pin "3") (pinfunction "3_3") (pintype "passive"))
      (node (ref "S251") (pin "3") (pinfunction "3_3") (pintype "passive"))
      (node (ref "S251_2") (pin "3") (pinfunction "3_3") (pintype "passive"))
      (node (ref "S252") (pin "3") (pinfunction "3_3") (pintype "passive"))
      (node (ref "S253") (pin "3") (pinfunction "3_3") (pintype "passive"))
      (node (ref "S254") (pin "3") (pinfunction "3_3") (pintype "passive"))
      (node (ref "S255") (pin "3") (pinfunction "3_3") (pintype "passive"))
      (node (ref "S256") (pin "3") (pinfunction "3_3") (pintype "passive"))
      (node (ref "S257") (pin "3") (pinfunction "3_3") (pintype "passive"))
      (node (ref "S258") (pin "3") (pinfunction "3_3") (pintype "passive"))
      (node (ref "S259") (pin "3") (pinfunction "3_3") (pintype "passive"))
      (node (ref "S260") (pin "3") (pinfunction "3_3") (pintype "passive"))
      (node (ref "S261") (pin "3") (pinfunction "3_3") (pintype "passive"))
      (node (ref "S262") (pin "3") (pinfunction "3_3") (pintype "passive"))
      (node (ref "S263") (pin "3") (pinfunction "3_3") (pintype "passive"))
      (node (ref "S263_2") (pin "3") (pinfunction "3_3") (pintype "passive"))
      (node (ref "S264") (pin "3") (pinfunction "3_3") (pintype "passive"))
      (node (ref "S264_2") (pin "3") (pinfunction "3_3") (pintype "passive"))
      (node (ref "S265") (pin "3") (pinfunction "3_3") (pintype "passive"))
      (node (ref "S265_2") (pin "3") (pinfunction "3_3") (pintype "passive"))
      (node (ref "S266") (pin "3") (pinfunction "3_3") (pintype "passive"))
      (node (ref "S267") (pin "3") (pinfunction "3_3") (pintype "passive"))
      (node (ref "S268") (pin "3") (pinfunction "3_3") (pintype "passive"))
      (node (ref "S269") (pin "3") (pinfunction "3_3") (pintype "passive"))
      (node (ref "S270") (pin "3") (pinfunction "3_3") (pintype "passive"))
      (node (ref "S271") (pin "3") (pinfunction "3_3") (pintype "passive"))
      (node (ref "S272") (pin "3") (pinfunction "3_3") (pintype "passive"))
      (node (ref "S273") (pin "3") (pinfunction "3_3") (pintype "passive"))
      (node (ref "S274") (pin "3") (pinfunction "3_3") (pintype "passive"))
      (node (ref "S275") (pin "3") (pinfunction "3_3") (pintype "passive"))
      (node (ref "S276") (pin "3") (pinfunction "3_3") (pintype "passive"))
      (node (ref "S277") (pin "3") (pinfunction "3_3") (pintype "passive"))
      (node (ref "S277_2") (pin "3") (pinfunction "3_3") (pintype "passive"))
      (node (ref "S278") (pin "3") (pinfunction "3_3") (pintype "passive"))
      (node (ref "S279") (pin "3") (pinfunction "3_3") (pintype "passive"))
      (node (ref "S280") (pin "3") (pinfunction "3_3") (pintype "passive"))
      (node (ref "S281") (pin "3") (pinfunction "3_3") (pintype "passive"))
      (node (ref "S282") (pin "3") (pinfunction "3_3") (pintype "passive"))
      (node (ref "S283") (pin "3") (pinfunction "3_3") (pintype "passive"))
      (node (ref "S284") (pin "3") (pinfunction "3_3") (pintype "passive"))
      (node (ref "S285") (pin "3") (pinfunction "3_3") (pintype "passive"))
      (node (ref "S286") (pin "3") (pinfunction "3_3") (pintype "passive"))
      (node (ref "S287") (pin "3") (pinfunction "3_3") (pintype "passive"))
      (node (ref "S288") (pin "3") (pinfunction "3_3") (pintype "passive"))
      (node (ref "S289") (pin "3") (pinfunction "3_3") (pintype "passive"))
      (node (ref "S290") (pin "3") (pinfunction "3_3") (pintype "passive"))
      (node (ref "S291") (pin "3") (pinfunction "3_3") (pintype "passive"))
    )
  )
)
